# clock-controller.net
KiCad netlist of a schematic drawn in EAGLE
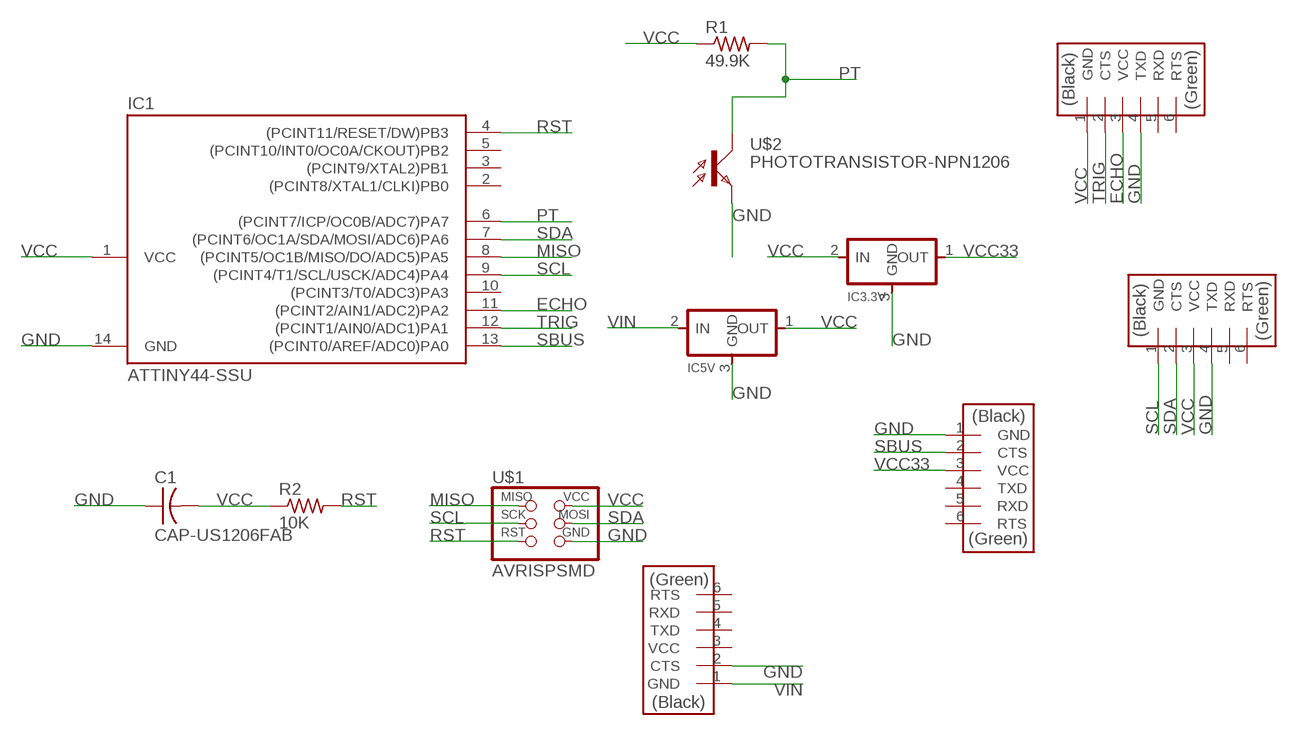
[diagram p0: schematic, sheet 1]

(export (version "E")
  (design (tool "Eeschema 10.0.6"))
  (components
    (comp (ref "C1")
      (value "CAP-US1206FAB")
      (footprint "eagle-import:C1206FAB")
      (libsource (lib "eagle-import") (part "CAP-US1206FAB"))
    )
    (comp (ref "DIGITS")
      (value "FTDI-SMD-HEADER")
      (footprint "eagle-import:1X06SMD")
      (libsource (lib "eagle-import") (part "FTDI-SMD-HEADER"))
    )
    (comp (ref "IC1")
      (value "ATTINY44-SSU")
      (footprint "eagle-import:SOIC14")
      (libsource (lib "eagle-import") (part "ATTINY44-SSU"))
    )
    (comp (ref "IC3.3V")
      (value "REGULATORSOT23")
      (footprint "eagle-import:SOT23")
      (libsource (lib "eagle-import") (part "REGULATORSOT23"))
    )
    (comp (ref "IC5V")
      (value "REGULATORSOT23")
      (footprint "eagle-import:SOT23")
      (libsource (lib "eagle-import") (part "REGULATORSOT23"))
    )
    (comp (ref "R1")
      (value "49.9K")
      (footprint "eagle-import:R1206FAB")
      (libsource (lib "eagle-import") (part "RES-US1206FAB"))
    )
    (comp (ref "R2")
      (value "10K")
      (footprint "eagle-import:R1206FAB")
      (libsource (lib "eagle-import") (part "RES-US1206FAB"))
    )
    (comp (ref "RTC")
      (value "FTDI-SMD-HEADER")
      (footprint "eagle-import:1X06SMD")
      (libsource (lib "eagle-import") (part "FTDI-SMD-HEADER"))
    )
    (comp (ref "U$1")
      (value "AVRISPSMD")
      (footprint "eagle-import:2X03SMD")
      (libsource (lib "eagle-import") (part "AVRISPSMD"))
    )
    (comp (ref "U$2")
      (value "PHOTOTRANSISTOR-NPN1206")
      (footprint "eagle-import:OP1206")
      (libsource (lib "eagle-import") (part "PHOTOTRANSISTOR-NPN1206"))
    )
    (comp (ref "ULTRA")
      (value "FTDI-SMD-HEADER")
      (footprint "eagle-import:1X06SMD")
      (libsource (lib "eagle-import") (part "FTDI-SMD-HEADER"))
    )
    (comp (ref "USB")
      (value "FTDI-SMD-HEADER")
      (footprint "eagle-import:1X06SMD")
      (libsource (lib "eagle-import") (part "FTDI-SMD-HEADER"))
    )
  )
  (nets
    (net (code "1") (name "/ECHO") (class "Default")
      (node (ref "IC1") (pin "11") (pinfunction "(PCINT2/AIN1/ADC2)PA2_11") (pintype "bidirectional"))
      (node (ref "ULTRA") (pin "3") (pinfunction "VCC_3") (pintype "bidirectional"))
    )
    (net (code "2") (name "/GND") (class "Default")
      (node (ref "C1") (pin "1") (pinfunction "1_1") (pintype "passive"))
      (node (ref "DIGITS") (pin "1") (pinfunction "GND_1") (pintype "bidirectional"))
      (node (ref "IC1") (pin "14") (pinfunction "GND_14") (pintype "power_in"))
      (node (ref "IC3.3V") (pin "3") (pinfunction "GND_3") (pintype "bidirectional"))
      (node (ref "IC5V") (pin "3") (pinfunction "GND_3") (pintype "bidirectional"))
      (node (ref "RTC") (pin "4") (pinfunction "TXD_4") (pintype "bidirectional"))
      (node (ref "U$1") (pin "6") (pinfunction "GND_6") (pintype "passive"))
      (node (ref "U$2") (pin "EMITTER") (pinfunction "E_EMITTER") (pintype "passive"))
      (node (ref "ULTRA") (pin "4") (pinfunction "TXD_4") (pintype "bidirectional"))
      (node (ref "USB") (pin "2") (pinfunction "CTS_2") (pintype "bidirectional"))
    )
    (net (code "3") (name "/MISO") (class "Default")
      (node (ref "IC1") (pin "8") (pinfunction "(PCINT5/OC1B/MISO/DO/ADC5)PA5_8") (pintype "bidirectional"))
      (node (ref "U$1") (pin "1") (pinfunction "MISO_1") (pintype "passive"))
    )
    (net (code "4") (name "/PT") (class "Default")
      (node (ref "IC1") (pin "6") (pinfunction "(PCINT7/ICP/OC0B/ADC7)PA7_6") (pintype "bidirectional"))
      (node (ref "R1") (pin "2") (pinfunction "2_2") (pintype "passive"))
      (node (ref "U$2") (pin "COLLECTOR") (pinfunction "C_COLLECTOR") (pintype "passive"))
    )
    (net (code "5") (name "/RST") (class "Default")
      (node (ref "IC1") (pin "4") (pinfunction "(PCINT11/RESET/DW)PB3_4") (pintype "bidirectional"))
      (node (ref "R2") (pin "2") (pinfunction "2_2") (pintype "passive"))
      (node (ref "U$1") (pin "5") (pinfunction "RST_5") (pintype "passive"))
    )
    (net (code "6") (name "/SBUS") (class "Default")
      (node (ref "DIGITS") (pin "2") (pinfunction "CTS_2") (pintype "bidirectional"))
      (node (ref "IC1") (pin "13") (pinfunction "(PCINT0/AREF/ADC0)PA0_13") (pintype "bidirectional"))
    )
    (net (code "7") (name "/SCL") (class "Default")
      (node (ref "IC1") (pin "9") (pinfunction "(PCINT4/T1/SCL/USCK/ADC4)PA4_9") (pintype "bidirectional"))
      (node (ref "RTC") (pin "1") (pinfunction "GND_1") (pintype "bidirectional"))
      (node (ref "U$1") (pin "3") (pinfunction "SCK_3") (pintype "passive"))
    )
    (net (code "8") (name "/SDA") (class "Default")
      (node (ref "IC1") (pin "7") (pinfunction "(PCINT6/OC1A/SDA/MOSI/ADC6)PA6_7") (pintype "bidirectional"))
      (node (ref "RTC") (pin "2") (pinfunction "CTS_2") (pintype "bidirectional"))
      (node (ref "U$1") (pin "4") (pinfunction "MOSI_4") (pintype "passive"))
    )
    (net (code "9") (name "/TRIG") (class "Default")
      (node (ref "IC1") (pin "12") (pinfunction "(PCINT1/AIN0/ADC1)PA1_12") (pintype "bidirectional"))
      (node (ref "ULTRA") (pin "2") (pinfunction "CTS_2") (pintype "bidirectional"))
    )
    (net (code "10") (name "/VCC") (class "Default")
      (node (ref "C1") (pin "2") (pinfunction "2_2") (pintype "passive"))
      (node (ref "IC1") (pin "1") (pinfunction "VCC_1") (pintype "power_in"))
      (node (ref "IC3.3V") (pin "2") (pinfunction "IN_2") (pintype "bidirectional"))
      (node (ref "IC5V") (pin "1") (pinfunction "OUT_1") (pintype "bidirectional"))
      (node (ref "R1") (pin "1") (pinfunction "1_1") (pintype "passive"))
      (node (ref "R2") (pin "1") (pinfunction "1_1") (pintype "passive"))
      (node (ref "RTC") (pin "3") (pinfunction "VCC_3") (pintype "bidirectional"))
      (node (ref "U$1") (pin "2") (pinfunction "VCC_2") (pintype "passive"))
      (node (ref "ULTRA") (pin "1") (pinfunction "GND_1") (pintype "bidirectional"))
    )
    (net (code "11") (name "/VCC33") (class "Default")
      (node (ref "DIGITS") (pin "3") (pinfunction "VCC_3") (pintype "bidirectional"))
      (node (ref "IC3.3V") (pin "1") (pinfunction "OUT_1") (pintype "bidirectional"))
    )
    (net (code "12") (name "/VIN") (class "Default")
      (node (ref "IC5V") (pin "2") (pinfunction "IN_2") (pintype "bidirectional"))
      (node (ref "USB") (pin "1") (pinfunction "GND_1") (pintype "bidirectional"))
    )
    (net (code "13") (name "unconnected-(DIGITS-RTS-Pad6)") (class "Default")
      (node (ref "DIGITS") (pin "6") (pinfunction "RTS_6") (pintype "bidirectional"))
    )
    (net (code "14") (name "unconnected-(DIGITS-RXD-Pad5)") (class "Default")
      (node (ref "DIGITS") (pin "5") (pinfunction "RXD_5") (pintype "bidirectional"))
    )
    (net (code "15") (name "unconnected-(DIGITS-TXD-Pad4)") (class "Default")
      (node (ref "DIGITS") (pin "4") (pinfunction "TXD_4") (pintype "bidirectional"))
    )
    (net (code "16") (name "unconnected-(IC1-(PCINT3{slash}T0{slash}ADC3)PA3-Pad10)") (class "Default")
      (node (ref "IC1") (pin "10") (pinfunction "(PCINT3/T0/ADC3)PA3_10") (pintype "bidirectional"))
    )
    (net (code "17") (name "unconnected-(IC1-(PCINT8{slash}XTAL1{slash}CLKI)PB0-Pad2)") (class "Default")
      (node (ref "IC1") (pin "2") (pinfunction "(PCINT8/XTAL1/CLKI)PB0_2") (pintype "bidirectional"))
    )
    (net (code "18") (name "unconnected-(IC1-(PCINT9{slash}XTAL2)PB1-Pad3)") (class "Default")
      (node (ref "IC1") (pin "3") (pinfunction "(PCINT9/XTAL2)PB1_3") (pintype "bidirectional"))
    )
    (net (code "19") (name "unconnected-(IC1-(PCINT10{slash}INT0{slash}OC0A{slash}CKOUT)PB2-Pad5)") (class "Default")
      (node (ref "IC1") (pin "5") (pinfunction "(PCINT10/INT0/OC0A/CKOUT)PB2_5") (pintype "bidirectional"))
    )
    (net (code "20") (name "unconnected-(RTC-RTS-Pad6)") (class "Default")
      (node (ref "RTC") (pin "6") (pinfunction "RTS_6") (pintype "bidirectional"))
    )
    (net (code "21") (name "unconnected-(RTC-RXD-Pad5)") (class "Default")
      (node (ref "RTC") (pin "5") (pinfunction "RXD_5") (pintype "bidirectional"))
    )
    (net (code "22") (name "unconnected-(ULTRA-RTS-Pad6)") (class "Default")
      (node (ref "ULTRA") (pin "6") (pinfunction "RTS_6") (pintype "bidirectional"))
    )
    (net (code "23") (name "unconnected-(ULTRA-RXD-Pad5)") (class "Default")
      (node (ref "ULTRA") (pin "5") (pinfunction "RXD_5") (pintype "bidirectional"))
    )
    (net (code "24") (name "unconnected-(USB-RTS-Pad6)") (class "Default")
      (node (ref "USB") (pin "6") (pinfunction "RTS_6") (pintype "bidirectional"))
    )
    (net (code "25") (name "unconnected-(USB-RXD-Pad5)") (class "Default")
      (node (ref "USB") (pin "5") (pinfunction "RXD_5") (pintype "bidirectional"))
    )
    (net (code "26") (name "unconnected-(USB-TXD-Pad4)") (class "Default")
      (node (ref "USB") (pin "4") (pinfunction "TXD_4") (pintype "bidirectional"))
    )
    (net (code "27") (name "unconnected-(USB-VCC-Pad3)") (class "Default")
      (node (ref "USB") (pin "3") (pinfunction "VCC_3") (pintype "bidirectional"))
    )
  )
)
